# Ext_sensors.net
KiCad netlist of a schematic drawn in EasyEDA Pro
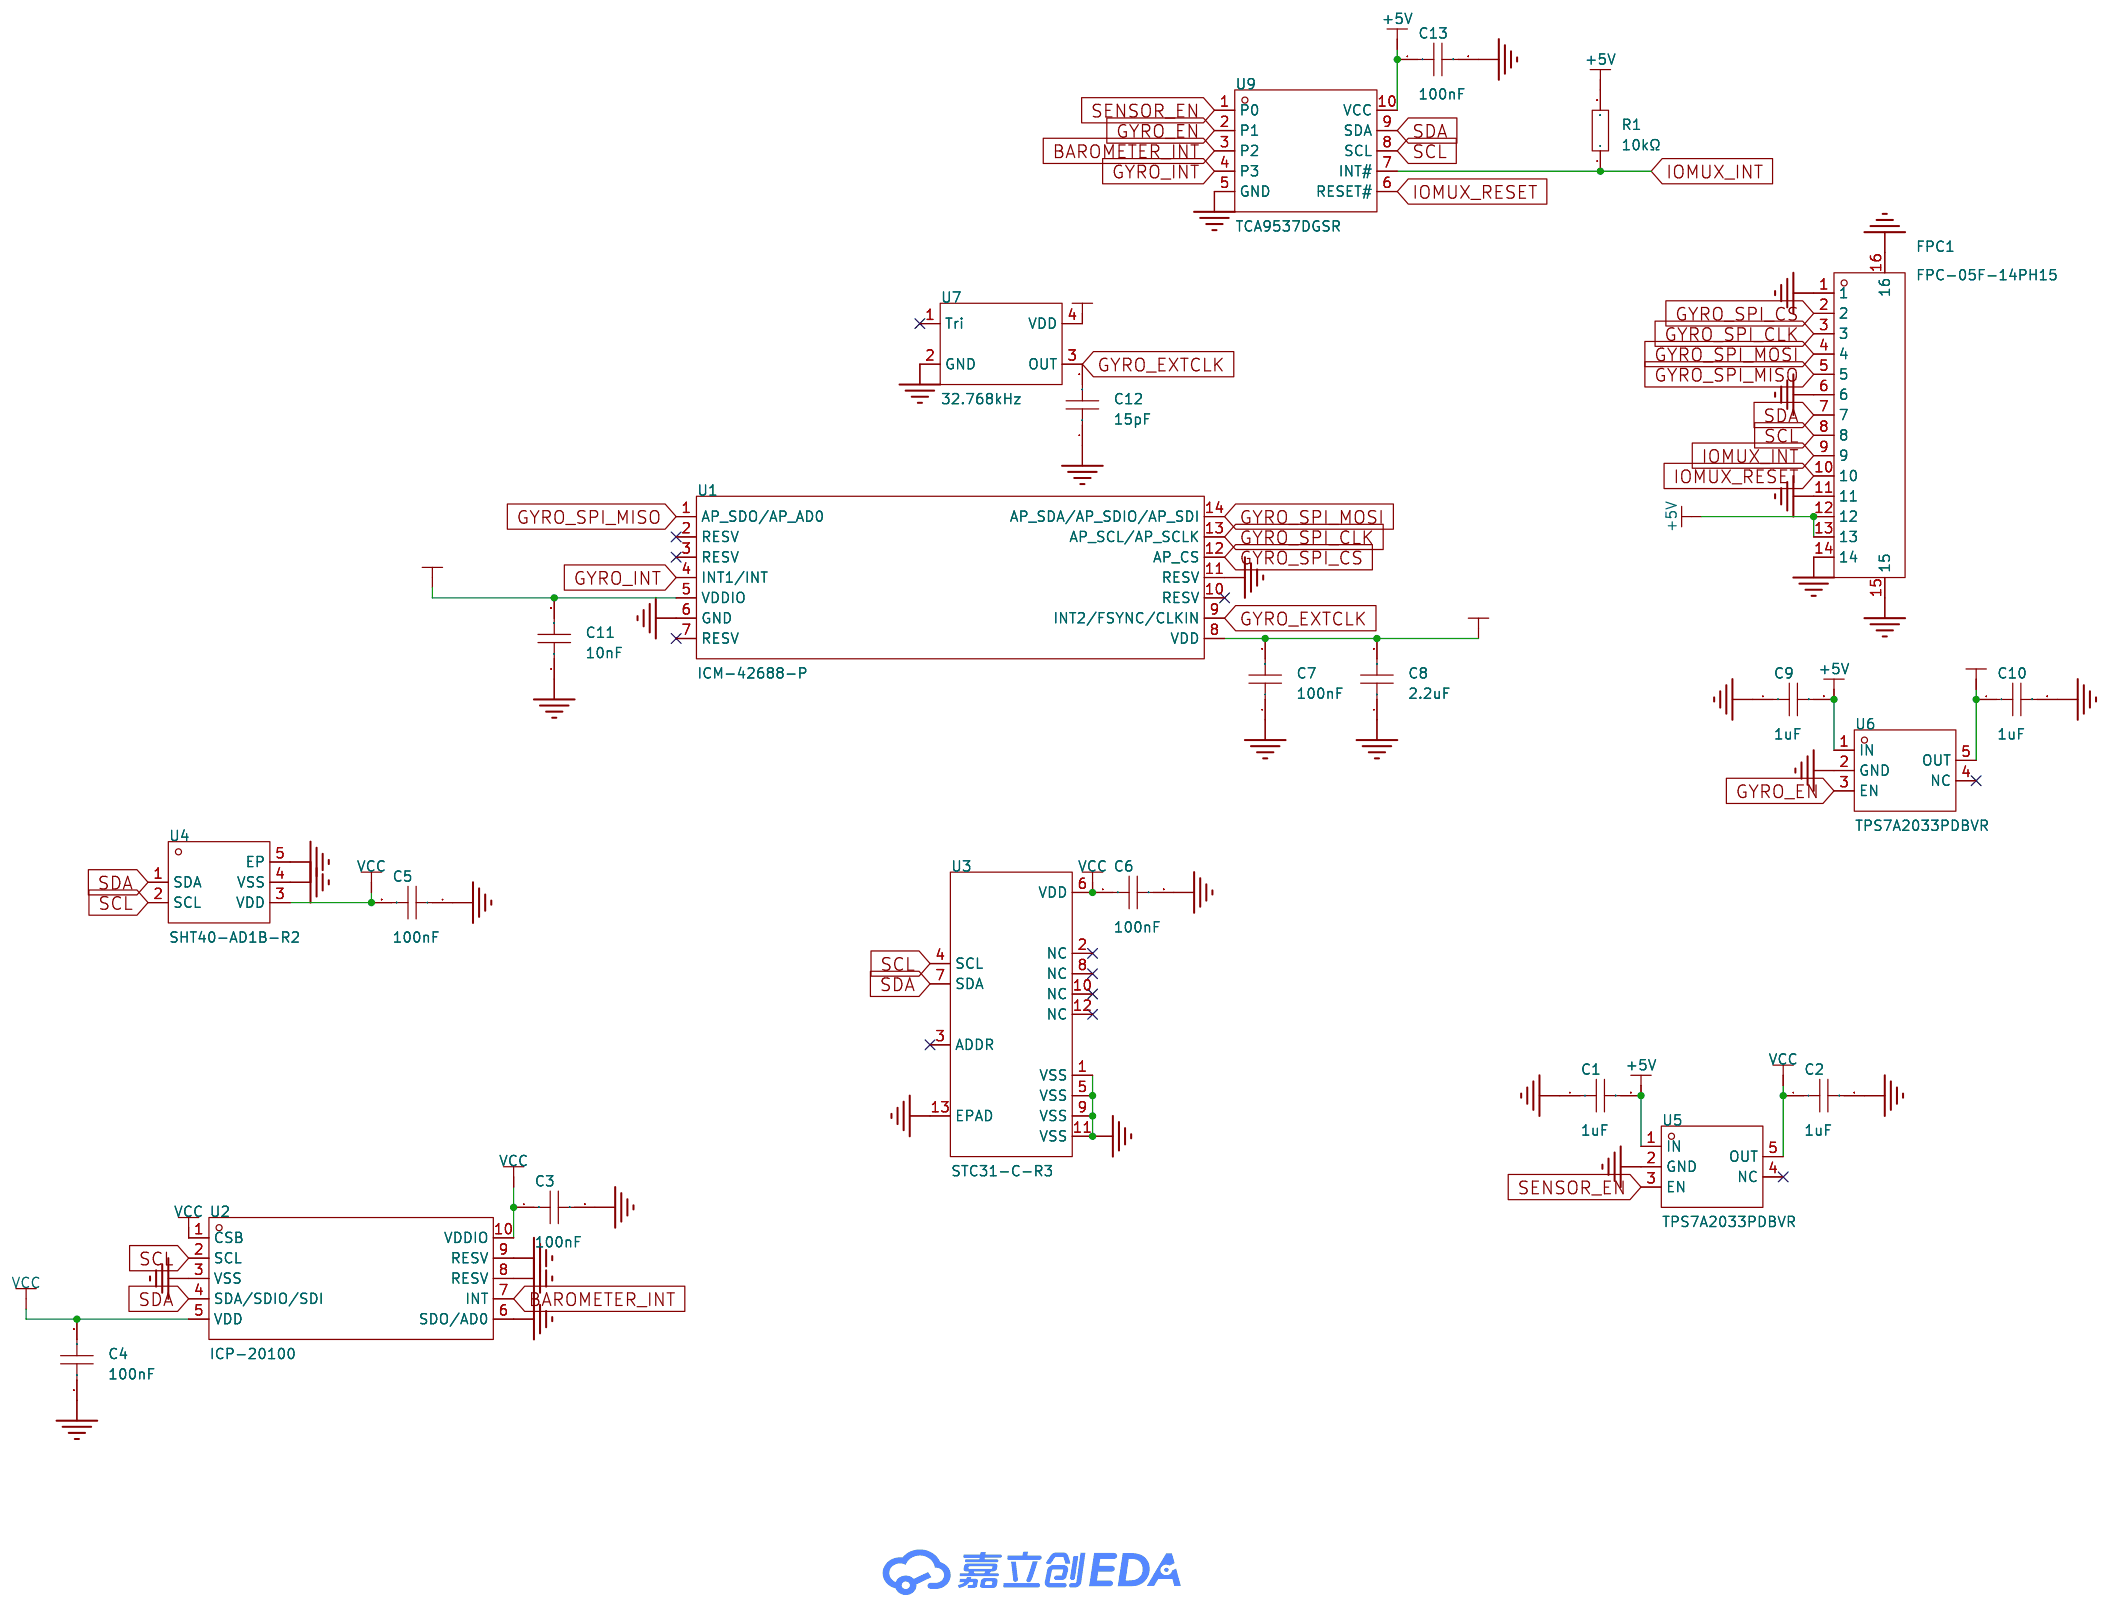
[diagram p0: schematic sheet]

(export (version "E")
  (design (tool "Eeschema 10.0.6"))
  (components
    (comp (ref "C1")
      (value "1uF")
      (footprint "easyedapro:C0603")
      (fields
        (field (name "Manufacturer Part") "GRM033R61A105ME44D")
        (field (name "Manufacturer") "muRata(村田)")
      )
      (libsource (lib "easyedapro") (part "Capacitance"))
    )
    (comp (ref "C2")
      (value "1uF")
      (footprint "easyedapro:C0603")
      (fields
        (field (name "Manufacturer Part") "GRM033R61A105ME44D")
        (field (name "Manufacturer") "muRata(村田)")
      )
      (libsource (lib "easyedapro") (part "Capacitance"))
    )
    (comp (ref "C3")
      (value "100nF")
      (footprint "easyedapro:C0603")
      (fields
        (field (name "Manufacturer Part") "GRM022R60J104KE15D")
        (field (name "Manufacturer") "muRata(村田)")
      )
      (libsource (lib "easyedapro") (part "Capacitance"))
    )
    (comp (ref "C4")
      (value "100nF")
      (footprint "easyedapro:C0603")
      (fields
        (field (name "Manufacturer Part") "GRM022R60J104KE15D")
        (field (name "Manufacturer") "muRata(村田)")
      )
      (libsource (lib "easyedapro") (part "Capacitance"))
    )
    (comp (ref "C5")
      (value "100nF")
      (footprint "easyedapro:C0603")
      (fields
        (field (name "Manufacturer Part") "GRM022R60J104KE15D")
        (field (name "Manufacturer") "muRata(村田)")
      )
      (libsource (lib "easyedapro") (part "Capacitance"))
    )
    (comp (ref "C6")
      (value "100nF")
      (footprint "easyedapro:C0603")
      (fields
        (field (name "Manufacturer Part") "GRM022R60J104KE15D")
        (field (name "Manufacturer") "muRata(村田)")
      )
      (libsource (lib "easyedapro") (part "Capacitance"))
    )
    (comp (ref "C7")
      (value "100nF")
      (footprint "easyedapro:C0603")
      (fields
        (field (name "Manufacturer Part") "GRM022R60J104KE15D")
        (field (name "Manufacturer") "muRata(村田)")
      )
      (libsource (lib "easyedapro") (part "Capacitance"))
    )
    (comp (ref "C8")
      (value "2.2uF")
      (footprint "easyedapro:C0603")
      (fields
        (field (name "Manufacturer Part") "GRM033R61A225ME47D")
        (field (name "Manufacturer") "muRata(村田)")
      )
      (libsource (lib "easyedapro") (part "Capacitance"))
    )
    (comp (ref "C9")
      (value "1uF")
      (footprint "easyedapro:C0603")
      (fields
        (field (name "Manufacturer Part") "GRM033R61A105ME44D")
        (field (name "Manufacturer") "muRata(村田)")
      )
      (libsource (lib "easyedapro") (part "Capacitance"))
    )
    (comp (ref "C10")
      (value "1uF")
      (footprint "easyedapro:C0603")
      (fields
        (field (name "Manufacturer Part") "GRM033R61A105ME44D")
        (field (name "Manufacturer") "muRata(村田)")
      )
      (libsource (lib "easyedapro") (part "Capacitance"))
    )
    (comp (ref "C11")
      (value "10nF")
      (footprint "easyedapro:C0603")
      (fields
        (field (name "Manufacturer Part") "CL02A103KQ2NNXC")
        (field (name "Manufacturer") "SAMSUNG(三星)")
      )
      (libsource (lib "easyedapro") (part "Capacitance"))
    )
    (comp (ref "C12")
      (value "15pF")
      (footprint "easyedapro:C0603")
      (fields
        (field (name "Manufacturer Part") "CC0100JRNPO6BN150")
        (field (name "Manufacturer") "YAGEO(国巨)")
      )
      (libsource (lib "easyedapro") (part "Capacitance"))
    )
    (comp (ref "C13")
      (value "100nF")
      (footprint "easyedapro:C0603")
      (fields
        (field (name "Manufacturer Part") "GRM022R60J104KE15D")
        (field (name "Manufacturer") "muRata(村田)")
      )
      (libsource (lib "easyedapro") (part "Capacitance"))
    )
    (comp (ref "FPC1")
      (value "FPC-05F-14PH15")
      (footprint "easyedapro:FPC-SMD_14P-P0.50_XUNPU_FPC-05F-14PH15")
      (description "锁定特性:翻盖式;触点类型:下接;触点数量:14P;间距:0.5mm;安装类型:卧贴;工作温度范围:-25°C~+85°C;")
      (fields (field (name "Manufacturer") "XUNPU(讯普)"))
      (libsource (lib "easyedapro") (part "FPC-05F-14PH15"))
    )
    (comp (ref "R1")
      (value "10kΩ")
      (footprint "easyedapro:R0603")
      (fields
        (field (name "Manufacturer Part") "0201WMF1002TEE")
        (field (name "Manufacturer") "UNI-ROYAL(厚声)")
      )
      (libsource (lib "easyedapro") (part "电阻"))
    )
    (comp (ref "U1")
      (value "ICM-42688-P")
      (footprint "easyedapro:LGA-14_L3.0-W2.5-P0.50-TL")
      (description "传感器类型:加速度计陀螺仪;")
      (fields (field (name "Manufacturer") "TDK InvenSense(应美盛)"))
      (libsource (lib "easyedapro") (part "ICM-42688-P"))
    )
    (comp (ref "U2")
      (value "ICP-20100")
      (footprint "easyedapro:LGA-10_L2.0-W2.0-P0.50-TL_ICP-20100")
      (fields (field (name "Manufacturer") "TDK InvenSense(应美盛)"))
      (libsource (lib "easyedapro") (part "ICP-20100"))
    )
    (comp (ref "U3")
      (value "STC31-C-R3")
      (footprint "easyedapro:QFN-12_L3.5-W3.0-P0.80-BL-EP")
      (description "二氧化碳气体浓度传感器")
      (fields (field (name "Manufacturer") "Sensirion(瑞士盛思锐)"))
      (libsource (lib "easyedapro") (part "STC31-C-R3"))
    )
    (comp (ref "U4")
      (value "SHT40-AD1B-R2")
      (footprint "easyedapro:DFN-4_L1.5-W1.5-P0.8-TL-EP")
      (description "±1.8% / max. ±3.5% RH 数字温湿度传感器")
      (fields (field (name "Manufacturer") "Sensirion(瑞士盛思锐)"))
      (libsource (lib "easyedapro") (part "SHT40-AD1B-R2"))
    )
    (comp (ref "U5")
      (value "TPS7A2033PDBVR")
      (footprint "easyedapro:SOT-23-5_L2.9-W1.6-P0.95-LS2.8-BR")
      (description "输出类型:固定;最大输入电压:6V;输出电压:3.3V;输出电流:300mA;输出极性:正极;")
      (fields (field (name "Manufacturer") "TI(德州仪器)"))
      (libsource (lib "easyedapro") (part "TPS7A2033PDBVR"))
    )
    (comp (ref "U6")
      (value "TPS7A2033PDBVR")
      (footprint "easyedapro:SOT-23-5_L2.9-W1.6-P0.95-LS2.8-BR")
      (description "输出类型:固定;最大输入电压:6V;输出电压:3.3V;输出电流:300mA;输出极性:正极;")
      (fields (field (name "Manufacturer") "TI(德州仪器)"))
      (libsource (lib "easyedapro") (part "TPS7A2033PDBVR"))
    )
    (comp (ref "U7")
      (value "32.768kHz")
      (footprint "easyedapro:OSC-SMD_4P-L3.2-W2.5-BL-CXC3X260000GHVRT3R")
      (description "频率:32.768kHz;常温频差:±10ppm;输出模式:CMOS;工作电压:3.3V;工作电流:7.2uA;频率稳定度:±20ppm;")
      (fields
        (field (name "Manufacturer Part") "SX3M32.768KB10F20TLN")
        (field (name "Manufacturer") "SCTF(星通时频)")
      )
      (libsource (lib "easyedapro") (part "SX3M32.768KB10F20TLN"))
    )
    (comp (ref "U9")
      (value "TCA9537DGSR")
      (footprint "easyedapro:VSSOP-10_L3.0-W3.0-P0.50-LS4.9-BL")
      (description "接口类型:I2C;时钟频率(fc):1MHz;")
      (fields (field (name "Manufacturer") "TI(德州仪器)"))
      (libsource (lib "easyedapro") (part "TCA9537DGSR"))
    )
  )
  (nets
    (net (code "1") (name "+5V") (class "Default")
      (node (ref "C1") (pin "2") (pinfunction "2_2") (pintype "input"))
      (node (ref "C13") (pin "1") (pinfunction "1_1") (pintype "input"))
      (node (ref "C9") (pin "2") (pinfunction "2_2") (pintype "input"))
      (node (ref "FPC1") (pin "12") (pinfunction "12_12") (pintype "unspecified"))
      (node (ref "FPC1") (pin "13") (pinfunction "13_13") (pintype "unspecified"))
      (node (ref "R1") (pin "2") (pinfunction "2_2") (pintype "input"))
      (node (ref "U5") (pin "1") (pinfunction "IN_1") (pintype "unspecified"))
      (node (ref "U6") (pin "1") (pinfunction "IN_1") (pintype "unspecified"))
      (node (ref "U9") (pin "10") (pinfunction "VCC_10") (pintype "unspecified"))
    )
    (net (code "2") (name "BAROMETER_INT") (class "Default")
      (node (ref "U2") (pin "7") (pinfunction "INT_7") (pintype "unspecified"))
      (node (ref "U9") (pin "3") (pinfunction "P2_3") (pintype "unspecified"))
    )
    (net (code "3") (name "GND") (class "Default")
      (node (ref "C1") (pin "1") (pinfunction "1_1") (pintype "input"))
      (node (ref "C10") (pin "2") (pinfunction "2_2") (pintype "input"))
      (node (ref "C11") (pin "1") (pinfunction "1_1") (pintype "input"))
      (node (ref "C12") (pin "1") (pinfunction "1_1") (pintype "input"))
      (node (ref "C13") (pin "2") (pinfunction "2_2") (pintype "input"))
      (node (ref "C2") (pin "2") (pinfunction "2_2") (pintype "input"))
      (node (ref "C3") (pin "2") (pinfunction "2_2") (pintype "input"))
      (node (ref "C4") (pin "1") (pinfunction "1_1") (pintype "input"))
      (node (ref "C5") (pin "1") (pinfunction "1_1") (pintype "input"))
      (node (ref "C6") (pin "2") (pinfunction "2_2") (pintype "input"))
      (node (ref "C7") (pin "1") (pinfunction "1_1") (pintype "input"))
      (node (ref "C8") (pin "1") (pinfunction "1_1") (pintype "input"))
      (node (ref "C9") (pin "1") (pinfunction "1_1") (pintype "input"))
      (node (ref "FPC1") (pin "1") (pinfunction "1_1") (pintype "unspecified"))
      (node (ref "FPC1") (pin "11") (pinfunction "11_11") (pintype "unspecified"))
      (node (ref "FPC1") (pin "14") (pinfunction "14_14") (pintype "unspecified"))
      (node (ref "FPC1") (pin "15") (pinfunction "15_15") (pintype "unspecified"))
      (node (ref "FPC1") (pin "16") (pinfunction "16_16") (pintype "unspecified"))
      (node (ref "FPC1") (pin "6") (pinfunction "6_6") (pintype "unspecified"))
      (node (ref "U1") (pin "11") (pinfunction "RESV_11") (pintype "unspecified"))
      (node (ref "U1") (pin "6") (pinfunction "GND_6") (pintype "unspecified"))
      (node (ref "U2") (pin "3") (pinfunction "VSS_3") (pintype "unspecified"))
      (node (ref "U2") (pin "6") (pinfunction "SDO/AD0_6") (pintype "unspecified"))
      (node (ref "U2") (pin "8") (pinfunction "RESV_8") (pintype "unspecified"))
      (node (ref "U2") (pin "9") (pinfunction "RESV_9") (pintype "unspecified"))
      (node (ref "U3") (pin "1") (pinfunction "VSS_1") (pintype "unspecified"))
      (node (ref "U3") (pin "11") (pinfunction "VSS_11") (pintype "unspecified"))
      (node (ref "U3") (pin "13") (pinfunction "EPAD_13") (pintype "unspecified"))
      (node (ref "U3") (pin "5") (pinfunction "VSS_5") (pintype "unspecified"))
      (node (ref "U3") (pin "9") (pinfunction "VSS_9") (pintype "unspecified"))
      (node (ref "U4") (pin "4") (pinfunction "VSS_4") (pintype "unspecified"))
      (node (ref "U4") (pin "5") (pinfunction "EP_5") (pintype "unspecified"))
      (node (ref "U5") (pin "2") (pinfunction "GND_2") (pintype "unspecified"))
      (node (ref "U6") (pin "2") (pinfunction "GND_2") (pintype "unspecified"))
      (node (ref "U7") (pin "2") (pinfunction "GND_2") (pintype "unspecified"))
      (node (ref "U9") (pin "5") (pinfunction "GND_5") (pintype "unspecified"))
    )
    (net (code "4") (name "GYRO_EN") (class "Default")
      (node (ref "U6") (pin "3") (pinfunction "EN_3") (pintype "unspecified"))
      (node (ref "U9") (pin "2") (pinfunction "P1_2") (pintype "unspecified"))
    )
    (net (code "5") (name "GYRO_EXTCLK") (class "Default")
      (node (ref "C12") (pin "2") (pinfunction "2_2") (pintype "input"))
      (node (ref "U1") (pin "9") (pinfunction "INT2/FSYNC/CLKIN_9") (pintype "unspecified"))
      (node (ref "U7") (pin "3") (pinfunction "OUT_3") (pintype "unspecified"))
    )
    (net (code "6") (name "GYRO_INT") (class "Default")
      (node (ref "U1") (pin "4") (pinfunction "INT1/INT_4") (pintype "unspecified"))
      (node (ref "U9") (pin "4") (pinfunction "P3_4") (pintype "unspecified"))
    )
    (net (code "7") (name "GYRO_SPI_CLK") (class "Default")
      (node (ref "FPC1") (pin "3") (pinfunction "3_3") (pintype "unspecified"))
      (node (ref "U1") (pin "13") (pinfunction "AP_SCL/AP_SCLK_13") (pintype "unspecified"))
    )
    (net (code "8") (name "GYRO_SPI_CS") (class "Default")
      (node (ref "FPC1") (pin "2") (pinfunction "2_2") (pintype "unspecified"))
      (node (ref "U1") (pin "12") (pinfunction "AP_CS_12") (pintype "unspecified"))
    )
    (net (code "9") (name "GYRO_SPI_MISO") (class "Default")
      (node (ref "FPC1") (pin "5") (pinfunction "5_5") (pintype "unspecified"))
      (node (ref "U1") (pin "1") (pinfunction "AP_SDO/AP_AD0_1") (pintype "unspecified"))
    )
    (net (code "10") (name "GYRO_SPI_MOSI") (class "Default")
      (node (ref "FPC1") (pin "4") (pinfunction "4_4") (pintype "unspecified"))
      (node (ref "U1") (pin "14") (pinfunction "AP_SDA/AP_SDIO/AP_SDI_14") (pintype "unspecified"))
    )
    (net (code "11") (name "IOMUX_INT") (class "Default")
      (node (ref "FPC1") (pin "9") (pinfunction "9_9") (pintype "unspecified"))
      (node (ref "R1") (pin "1") (pinfunction "1_1") (pintype "input"))
      (node (ref "U9") (pin "7") (pinfunction "INT#_7") (pintype "unspecified"))
    )
    (net (code "12") (name "IOMUX_RESET") (class "Default")
      (node (ref "FPC1") (pin "10") (pinfunction "10_10") (pintype "unspecified"))
      (node (ref "U9") (pin "6") (pinfunction "RESET#_6") (pintype "unspecified"))
    )
    (net (code "13") (name "SCL") (class "Default")
      (node (ref "FPC1") (pin "8") (pinfunction "8_8") (pintype "unspecified"))
      (node (ref "U2") (pin "2") (pinfunction "SCL_2") (pintype "unspecified"))
      (node (ref "U3") (pin "4") (pinfunction "SCL_4") (pintype "unspecified"))
      (node (ref "U4") (pin "2") (pinfunction "SCL_2") (pintype "unspecified"))
      (node (ref "U9") (pin "8") (pinfunction "SCL_8") (pintype "unspecified"))
    )
    (net (code "14") (name "SDA") (class "Default")
      (node (ref "FPC1") (pin "7") (pinfunction "7_7") (pintype "unspecified"))
      (node (ref "U2") (pin "4") (pinfunction "SDA/SDIO/SDI_4") (pintype "unspecified"))
      (node (ref "U3") (pin "7") (pinfunction "SDA_7") (pintype "unspecified"))
      (node (ref "U4") (pin "1") (pinfunction "SDA_1") (pintype "unspecified"))
      (node (ref "U9") (pin "9") (pinfunction "SDA_9") (pintype "unspecified"))
    )
    (net (code "15") (name "SENSOR_EN") (class "Default")
      (node (ref "U5") (pin "3") (pinfunction "EN_3") (pintype "unspecified"))
      (node (ref "U9") (pin "1") (pinfunction "P0_1") (pintype "unspecified"))
    )
    (net (code "16") (name "VCC") (class "Default")
      (node (ref "C2") (pin "1") (pinfunction "1_1") (pintype "input"))
      (node (ref "C3") (pin "1") (pinfunction "1_1") (pintype "input"))
      (node (ref "C4") (pin "2") (pinfunction "2_2") (pintype "input"))
      (node (ref "C5") (pin "2") (pinfunction "2_2") (pintype "input"))
      (node (ref "C6") (pin "1") (pinfunction "1_1") (pintype "input"))
      (node (ref "U2") (pin "1") (pinfunction "CSB_1") (pintype "unspecified"))
      (node (ref "U2") (pin "10") (pinfunction "VDDIO_10") (pintype "unspecified"))
      (node (ref "U2") (pin "5") (pinfunction "VDD_5") (pintype "unspecified"))
      (node (ref "U3") (pin "6") (pinfunction "VDD_6") (pintype "unspecified"))
      (node (ref "U4") (pin "3") (pinfunction "VDD_3") (pintype "unspecified"))
      (node (ref "U5") (pin "5") (pinfunction "OUT_5") (pintype "unspecified"))
    )
    (net (code "17") (name "VCC1") (class "Default")
      (node (ref "C10") (pin "1") (pinfunction "1_1") (pintype "input"))
      (node (ref "C11") (pin "2") (pinfunction "2_2") (pintype "input"))
      (node (ref "C7") (pin "2") (pinfunction "2_2") (pintype "input"))
      (node (ref "C8") (pin "2") (pinfunction "2_2") (pintype "input"))
      (node (ref "U1") (pin "5") (pinfunction "VDDIO_5") (pintype "unspecified"))
      (node (ref "U1") (pin "8") (pinfunction "VDD_8") (pintype "unspecified"))
      (node (ref "U6") (pin "5") (pinfunction "OUT_5") (pintype "unspecified"))
      (node (ref "U7") (pin "4") (pinfunction "VDD_4") (pintype "unspecified"))
    )
    (net (code "18") (name "unconnected-(U1-RESV-Pad2)") (class "Default")
      (node (ref "U1") (pin "2") (pinfunction "RESV_2") (pintype "unspecified+no_connect"))
    )
    (net (code "19") (name "unconnected-(U1-RESV-Pad3)") (class "Default")
      (node (ref "U1") (pin "3") (pinfunction "RESV_3") (pintype "unspecified+no_connect"))
    )
    (net (code "20") (name "unconnected-(U1-RESV-Pad7)") (class "Default")
      (node (ref "U1") (pin "7") (pinfunction "RESV_7") (pintype "unspecified+no_connect"))
    )
    (net (code "21") (name "unconnected-(U1-RESV-Pad10)") (class "Default")
      (node (ref "U1") (pin "10") (pinfunction "RESV_10") (pintype "unspecified+no_connect"))
    )
    (net (code "22") (name "unconnected-(U3-ADDR-Pad3)") (class "Default")
      (node (ref "U3") (pin "3") (pinfunction "ADDR_3") (pintype "unspecified+no_connect"))
    )
    (net (code "23") (name "unconnected-(U3-NC-Pad2)") (class "Default")
      (node (ref "U3") (pin "2") (pinfunction "NC_2") (pintype "unspecified+no_connect"))
    )
    (net (code "24") (name "unconnected-(U3-NC-Pad8)") (class "Default")
      (node (ref "U3") (pin "8") (pinfunction "NC_8") (pintype "unspecified+no_connect"))
    )
    (net (code "25") (name "unconnected-(U3-NC-Pad10)") (class "Default")
      (node (ref "U3") (pin "10") (pinfunction "NC_10") (pintype "unspecified+no_connect"))
    )
    (net (code "26") (name "unconnected-(U3-NC-Pad12)") (class "Default")
      (node (ref "U3") (pin "12") (pinfunction "NC_12") (pintype "unspecified+no_connect"))
    )
    (net (code "27") (name "unconnected-(U5-NC-Pad4)") (class "Default")
      (node (ref "U5") (pin "4") (pinfunction "NC_4") (pintype "unspecified+no_connect"))
    )
    (net (code "28") (name "unconnected-(U6-NC-Pad4)") (class "Default")
      (node (ref "U6") (pin "4") (pinfunction "NC_4") (pintype "unspecified+no_connect"))
    )
    (net (code "29") (name "unconnected-(U7-Tri-Pad1)") (class "Default")
      (node (ref "U7") (pin "1") (pinfunction "Tri_1") (pintype "unspecified+no_connect"))
    )
  )
)
